# USER_IO.net
KiCad netlist of a schematic drawn in Altium Designer
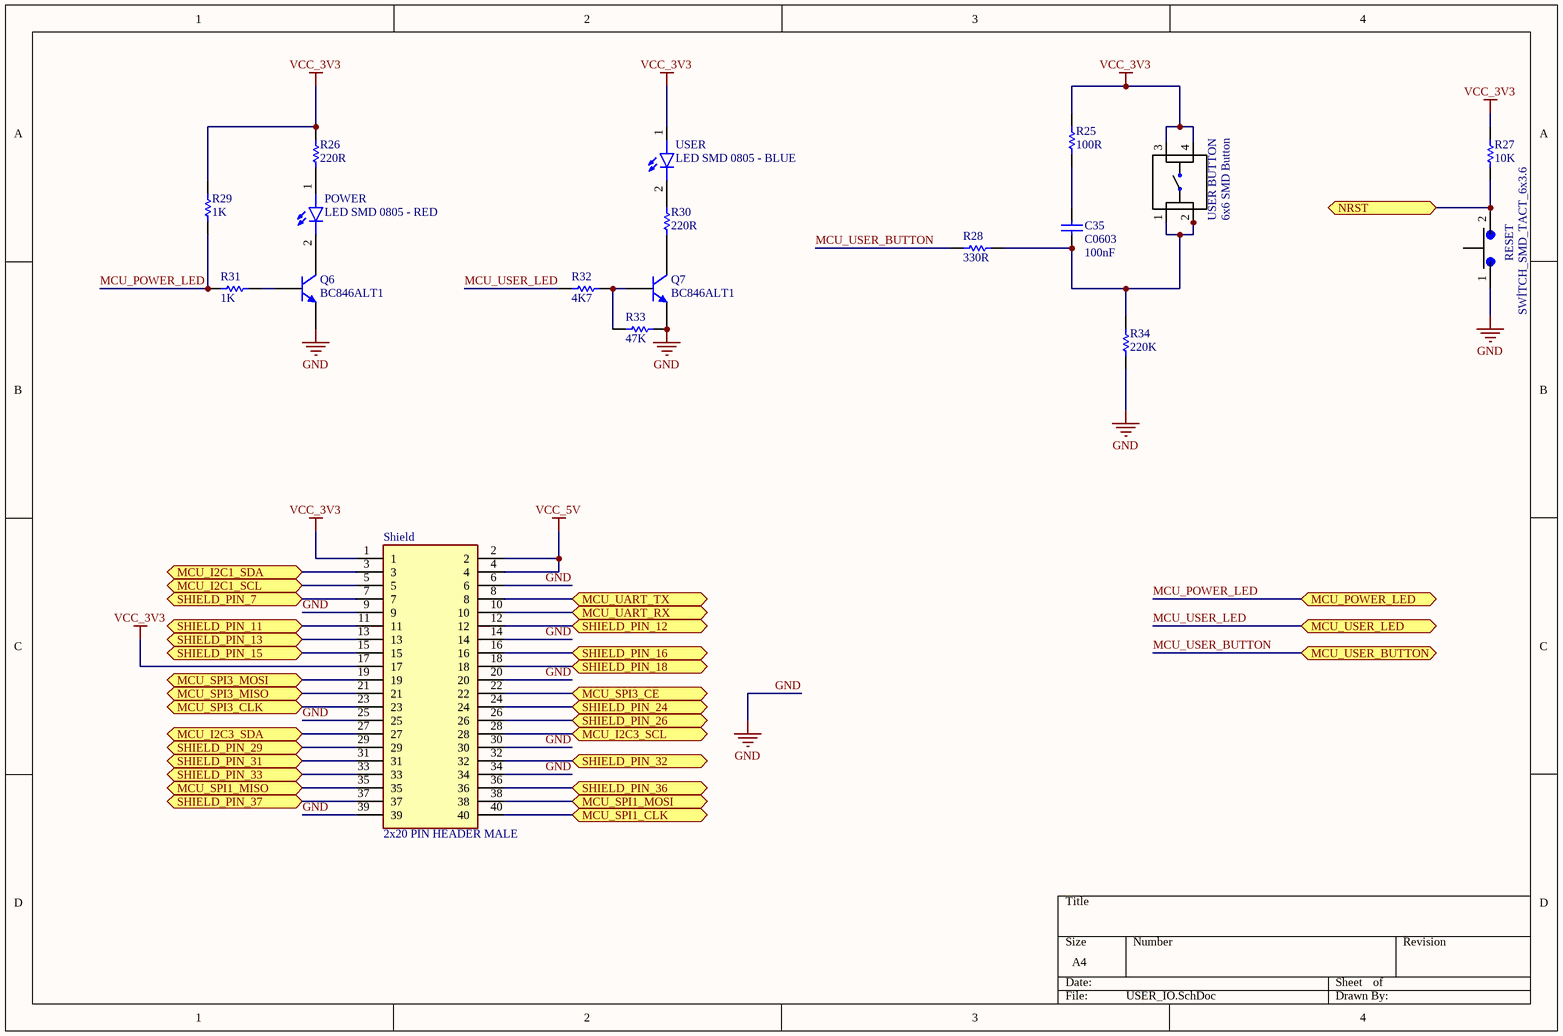
[diagram p0: USER_IO.SchDoc]

(export (version "E")
  (design (tool "Eeschema 10.0.6"))
  (components
    (comp (ref "C35")
      (value "C0603")
      (footprint "C0603")
      (description "Ceramic Chip Capacitor - Standard")
      (fields (field (name "ALTIUM_VALUE") "100nF") (field (name "PUBLISHER") "Altium Limited"))
      (libsource (lib "haberlesme") (part "C0603"))
    )
    (comp (ref "POWER")
      (value "LED SMD 0805 - RED")
      (footprint "LED SMD 0805 - RED")
      (libsource (lib "haberlesme") (part "LED SMD 0805 - RED"))
    )
    (comp (ref "Q6")
      (value "BC846ALT1")
      (footprint "BC846")
      (description "General Purpose Transistor NPN Silicon")
      (fields (field (name "PUBLISHER") "Altium Limited"))
      (libsource (lib "Motorola Discrete BJT") (part "BC846ALT1"))
    )
    (comp (ref "Q7")
      (value "BC846ALT1")
      (footprint "BC846")
      (description "General Purpose Transistor NPN Silicon")
      (fields (field (name "PUBLISHER") "Altium Limited"))
      (libsource (lib "Motorola Discrete BJT") (part "BC846ALT1"))
    )
    (comp (ref "R25")
      (value "100R")
      (footprint "Isbak:CC1608-0603")
      (description "Resistor")
      (fields
        (field (name "MANUFACTURER") "Generic Components")
        (field (name "Comment") "Res0603")
        (field (name "PUBLISHER") "Altium Limited")
      )
      (libsource (lib "Isbak") (part "Res0603"))
    )
    (comp (ref "R26")
      (value "220R")
      (footprint "Isbak:CC1608-0603")
      (description "Resistor")
      (fields
        (field (name "MANUFACTURER") "Generic Components")
        (field (name "Comment") "Res0603")
        (field (name "PUBLISHER") "Altium Limited")
      )
      (libsource (lib "Isbak") (part "Res0603"))
    )
    (comp (ref "R27")
      (value "10K")
      (footprint "Isbak:CC1608-0603")
      (description "Resistor")
      (fields
        (field (name "MANUFACTURER") "Generic Components")
        (field (name "Comment") "Res0603")
        (field (name "PUBLISHER") "Altium Limited")
      )
      (libsource (lib "Isbak") (part "Res0603"))
    )
    (comp (ref "R28")
      (value "330R")
      (footprint "Isbak:CC1608-0603")
      (description "Resistor")
      (fields
        (field (name "MANUFACTURER") "Generic Components")
        (field (name "Comment") "Res0603")
        (field (name "PUBLISHER") "Altium Limited")
      )
      (libsource (lib "Isbak") (part "Res0603"))
    )
    (comp (ref "R29")
      (value "1K")
      (footprint "Isbak:CC1608-0603")
      (description "Resistor")
      (fields
        (field (name "MANUFACTURER") "Generic Components")
        (field (name "Comment") "Res0603")
        (field (name "PUBLISHER") "Altium Limited")
      )
      (libsource (lib "Isbak") (part "Res0603"))
    )
    (comp (ref "R30")
      (value "220R")
      (footprint "Isbak:CC1608-0603")
      (description "Resistor")
      (fields
        (field (name "MANUFACTURER") "Generic Components")
        (field (name "Comment") "Res0603")
        (field (name "PUBLISHER") "Altium Limited")
      )
      (libsource (lib "Isbak") (part "Res0603"))
    )
    (comp (ref "R31")
      (value "1K")
      (footprint "Isbak:CC1608-0603")
      (description "Resistor")
      (fields
        (field (name "MANUFACTURER") "Generic Components")
        (field (name "Comment") "Res0603")
        (field (name "PUBLISHER") "Altium Limited")
      )
      (libsource (lib "Isbak") (part "Res0603"))
    )
    (comp (ref "R32")
      (value "4K7")
      (footprint "Isbak:CC1608-0603")
      (description "Resistor")
      (fields
        (field (name "MANUFACTURER") "Generic Components")
        (field (name "Comment") "Res0603")
        (field (name "PUBLISHER") "Altium Limited")
      )
      (libsource (lib "Isbak") (part "Res0603"))
    )
    (comp (ref "R33")
      (value "47K")
      (footprint "Isbak:CC1608-0603")
      (description "Resistor")
      (fields
        (field (name "MANUFACTURER") "Generic Components")
        (field (name "Comment") "Res0603")
        (field (name "PUBLISHER") "Altium Limited")
      )
      (libsource (lib "Isbak") (part "Res0603"))
    )
    (comp (ref "R34")
      (value "220K")
      (footprint "Isbak:CC1608-0603")
      (description "Resistor")
      (fields
        (field (name "MANUFACTURER") "Generic Components")
        (field (name "Comment") "Res0603")
        (field (name "PUBLISHER") "Altium Limited")
      )
      (libsource (lib "Isbak") (part "Res0603"))
    )
    (comp (ref "RESET")
      (value "SWİTCH_SMD_TACT_6x3.6")
      (footprint "SWİTCH_SMD_TACT_6X3.6")
      (libsource (lib "haberlesme") (part "SWİTCH_SMD_TACT_6x3.6"))
    )
    (comp (ref "Shield")
      (value "2x20 PIN HEADER MALE")
      (footprint "2x20 PIN HEADER MALE")
      (libsource (lib "haberlesme") (part "2x20 PIN HEADER MALE"))
    )
    (comp (ref "USER")
      (value "LED SMD 0805 - BLUE")
      (footprint "LED SMD 0805 - BLUE")
      (libsource (lib "haberlesme") (part "LED SMD 0805 - BLUE"))
    )
    (comp (ref "USER BUTTON")
      (value "6x6 SMD Button")
      (footprint "6x6 Smd Button")
      (libsource (lib "haberlesme") (part "6x6 SMD Button"))
    )
  )
  (nets
    (net (code "1") (name "/MCU_I2C1_SCL") (class "Default")
      (node (ref "Shield") (pin "5") (pinfunction "5_5") (pintype "passive"))
    )
    (net (code "2") (name "/MCU_I2C1_SDA") (class "Default")
      (node (ref "Shield") (pin "3") (pinfunction "3_3") (pintype "passive"))
    )
    (net (code "3") (name "/MCU_I2C3_SCL") (class "Default")
      (node (ref "Shield") (pin "28") (pinfunction "28_28") (pintype "passive"))
    )
    (net (code "4") (name "/MCU_I2C3_SDA") (class "Default")
      (node (ref "Shield") (pin "27") (pinfunction "27_27") (pintype "passive"))
    )
    (net (code "5") (name "/MCU_POWER_LED") (class "Default")
      (node (ref "R29") (pin "1") (pinfunction "1_1") (pintype "passive"))
      (node (ref "R31") (pin "2") (pinfunction "2_2") (pintype "passive"))
    )
    (net (code "6") (name "/MCU_SPI1_CLK") (class "Default")
      (node (ref "Shield") (pin "40") (pinfunction "40_40") (pintype "passive"))
    )
    (net (code "7") (name "/MCU_SPI1_MISO") (class "Default")
      (node (ref "Shield") (pin "35") (pinfunction "35_35") (pintype "passive"))
    )
    (net (code "8") (name "/MCU_SPI1_MOSI") (class "Default")
      (node (ref "Shield") (pin "38") (pinfunction "38_38") (pintype "passive"))
    )
    (net (code "9") (name "/MCU_SPI3_CE") (class "Default")
      (node (ref "Shield") (pin "22") (pinfunction "22_22") (pintype "passive"))
    )
    (net (code "10") (name "/MCU_SPI3_CLK") (class "Default")
      (node (ref "Shield") (pin "23") (pinfunction "23_23") (pintype "passive"))
    )
    (net (code "11") (name "/MCU_SPI3_MISO") (class "Default")
      (node (ref "Shield") (pin "21") (pinfunction "21_21") (pintype "passive"))
    )
    (net (code "12") (name "/MCU_SPI3_MOSI") (class "Default")
      (node (ref "Shield") (pin "19") (pinfunction "19_19") (pintype "passive"))
    )
    (net (code "13") (name "/MCU_UART_RX") (class "Default")
      (node (ref "Shield") (pin "10") (pinfunction "10_10") (pintype "passive"))
    )
    (net (code "14") (name "/MCU_UART_TX") (class "Default")
      (node (ref "Shield") (pin "8") (pinfunction "8_8") (pintype "passive"))
    )
    (net (code "15") (name "/MCU_USER_BUTTON") (class "Default")
      (node (ref "R28") (pin "2") (pinfunction "2_2") (pintype "passive"))
    )
    (net (code "16") (name "/MCU_USER_LED") (class "Default")
      (node (ref "R32") (pin "2") (pinfunction "2_2") (pintype "passive"))
    )
    (net (code "17") (name "/NRST") (class "Default")
      (node (ref "R27") (pin "2") (pinfunction "2_2") (pintype "passive"))
      (node (ref "RESET") (pin "2") (pinfunction "2_2") (pintype "passive"))
    )
    (net (code "18") (name "/SHIELD_PIN_7") (class "Default")
      (node (ref "Shield") (pin "7") (pinfunction "7_7") (pintype "passive"))
    )
    (net (code "19") (name "/SHIELD_PIN_11") (class "Default")
      (node (ref "Shield") (pin "11") (pinfunction "11_11") (pintype "passive"))
    )
    (net (code "20") (name "/SHIELD_PIN_12") (class "Default")
      (node (ref "Shield") (pin "12") (pinfunction "12_12") (pintype "passive"))
    )
    (net (code "21") (name "/SHIELD_PIN_13") (class "Default")
      (node (ref "Shield") (pin "13") (pinfunction "13_13") (pintype "passive"))
    )
    (net (code "22") (name "/SHIELD_PIN_15") (class "Default")
      (node (ref "Shield") (pin "15") (pinfunction "15_15") (pintype "passive"))
    )
    (net (code "23") (name "/SHIELD_PIN_16") (class "Default")
      (node (ref "Shield") (pin "16") (pinfunction "16_16") (pintype "passive"))
    )
    (net (code "24") (name "/SHIELD_PIN_18") (class "Default")
      (node (ref "Shield") (pin "18") (pinfunction "18_18") (pintype "passive"))
    )
    (net (code "25") (name "/SHIELD_PIN_24") (class "Default")
      (node (ref "Shield") (pin "24") (pinfunction "24_24") (pintype "passive"))
    )
    (net (code "26") (name "/SHIELD_PIN_26") (class "Default")
      (node (ref "Shield") (pin "26") (pinfunction "26_26") (pintype "passive"))
    )
    (net (code "27") (name "/SHIELD_PIN_29") (class "Default")
      (node (ref "Shield") (pin "29") (pinfunction "29_29") (pintype "passive"))
    )
    (net (code "28") (name "/SHIELD_PIN_31") (class "Default")
      (node (ref "Shield") (pin "31") (pinfunction "31_31") (pintype "passive"))
    )
    (net (code "29") (name "/SHIELD_PIN_32") (class "Default")
      (node (ref "Shield") (pin "32") (pinfunction "32_32") (pintype "passive"))
    )
    (net (code "30") (name "/SHIELD_PIN_33") (class "Default")
      (node (ref "Shield") (pin "33") (pinfunction "33_33") (pintype "passive"))
    )
    (net (code "31") (name "/SHIELD_PIN_36") (class "Default")
      (node (ref "Shield") (pin "36") (pinfunction "36_36") (pintype "passive"))
    )
    (net (code "32") (name "/SHIELD_PIN_37") (class "Default")
      (node (ref "Shield") (pin "37") (pinfunction "37_37") (pintype "passive"))
    )
    (net (code "33") (name "GND") (class "Default")
      (node (ref "Q6") (pin "2") (pinfunction "E_2") (pintype "passive"))
      (node (ref "Q7") (pin "2") (pinfunction "E_2") (pintype "passive"))
      (node (ref "R33") (pin "1") (pinfunction "1_1") (pintype "passive"))
      (node (ref "R34") (pin "1") (pinfunction "1_1") (pintype "passive"))
      (node (ref "RESET") (pin "1") (pinfunction "1_1") (pintype "passive"))
      (node (ref "Shield") (pin "14") (pinfunction "14_14") (pintype "passive"))
      (node (ref "Shield") (pin "20") (pinfunction "20_20") (pintype "passive"))
      (node (ref "Shield") (pin "25") (pinfunction "25_25") (pintype "passive"))
      (node (ref "Shield") (pin "30") (pinfunction "30_30") (pintype "passive"))
      (node (ref "Shield") (pin "34") (pinfunction "34_34") (pintype "passive"))
      (node (ref "Shield") (pin "39") (pinfunction "39_39") (pintype "passive"))
      (node (ref "Shield") (pin "6") (pinfunction "6_6") (pintype "passive"))
      (node (ref "Shield") (pin "9") (pinfunction "9_9") (pintype "passive"))
    )
    (net (code "34") (name "Net-(C35-Pad1)") (class "Default")
      (node (ref "C35") (pin "1") (pinfunction "1_1") (pintype "passive"))
      (node (ref "R28") (pin "1") (pinfunction "1_1") (pintype "passive"))
      (node (ref "R34") (pin "2") (pinfunction "2_2") (pintype "passive"))
      (node (ref "USER BUTTON") (pin "1") (pinfunction "1_1") (pintype "passive"))
      (node (ref "USER BUTTON") (pin "2") (pinfunction "2_2") (pintype "passive"))
    )
    (net (code "35") (name "Net-(C35-Pad2)") (class "Default")
      (node (ref "C35") (pin "2") (pinfunction "2_2") (pintype "passive"))
      (node (ref "R25") (pin "2") (pinfunction "2_2") (pintype "passive"))
    )
    (net (code "36") (name "Net-(POWER-Pad1)") (class "Default")
      (node (ref "POWER") (pin "1") (pinfunction "1_1") (pintype "passive"))
      (node (ref "R26") (pin "1") (pinfunction "1_1") (pintype "passive"))
    )
    (net (code "37") (name "Net-(Q6-B)") (class "Default")
      (node (ref "Q6") (pin "1") (pinfunction "B_1") (pintype "passive"))
      (node (ref "R31") (pin "1") (pinfunction "1_1") (pintype "passive"))
    )
    (net (code "38") (name "Net-(Q6-C)") (class "Default")
      (node (ref "POWER") (pin "2") (pinfunction "2_2") (pintype "passive"))
      (node (ref "Q6") (pin "3") (pinfunction "C_3") (pintype "passive"))
    )
    (net (code "39") (name "Net-(Q7-B)") (class "Default")
      (node (ref "Q7") (pin "1") (pinfunction "B_1") (pintype "passive"))
      (node (ref "R32") (pin "1") (pinfunction "1_1") (pintype "passive"))
      (node (ref "R33") (pin "2") (pinfunction "2_2") (pintype "passive"))
    )
    (net (code "40") (name "Net-(Q7-C)") (class "Default")
      (node (ref "Q7") (pin "3") (pinfunction "C_3") (pintype "passive"))
      (node (ref "R30") (pin "2") (pinfunction "2_2") (pintype "passive"))
    )
    (net (code "41") (name "Net-(R30-Pad1)") (class "Default")
      (node (ref "R30") (pin "1") (pinfunction "1_1") (pintype "passive"))
      (node (ref "USER") (pin "2") (pinfunction "2_2") (pintype "passive"))
    )
    (net (code "42") (name "VCC_3V3") (class "Default")
      (node (ref "R25") (pin "1") (pinfunction "1_1") (pintype "passive"))
      (node (ref "R26") (pin "2") (pinfunction "2_2") (pintype "passive"))
      (node (ref "R27") (pin "1") (pinfunction "1_1") (pintype "passive"))
      (node (ref "R29") (pin "2") (pinfunction "2_2") (pintype "passive"))
      (node (ref "Shield") (pin "1") (pinfunction "1_1") (pintype "passive"))
      (node (ref "Shield") (pin "17") (pinfunction "17_17") (pintype "passive"))
      (node (ref "USER") (pin "1") (pinfunction "1_1") (pintype "passive"))
      (node (ref "USER BUTTON") (pin "3") (pinfunction "3_3") (pintype "passive"))
      (node (ref "USER BUTTON") (pin "4") (pinfunction "4_4") (pintype "passive"))
    )
    (net (code "43") (name "VCC_5V") (class "Default")
      (node (ref "Shield") (pin "2") (pinfunction "2_2") (pintype "passive"))
      (node (ref "Shield") (pin "4") (pinfunction "4_4") (pintype "passive"))
    )
  )
)
